# Shematic.net
KiCad netlist of a schematic drawn in EAGLE
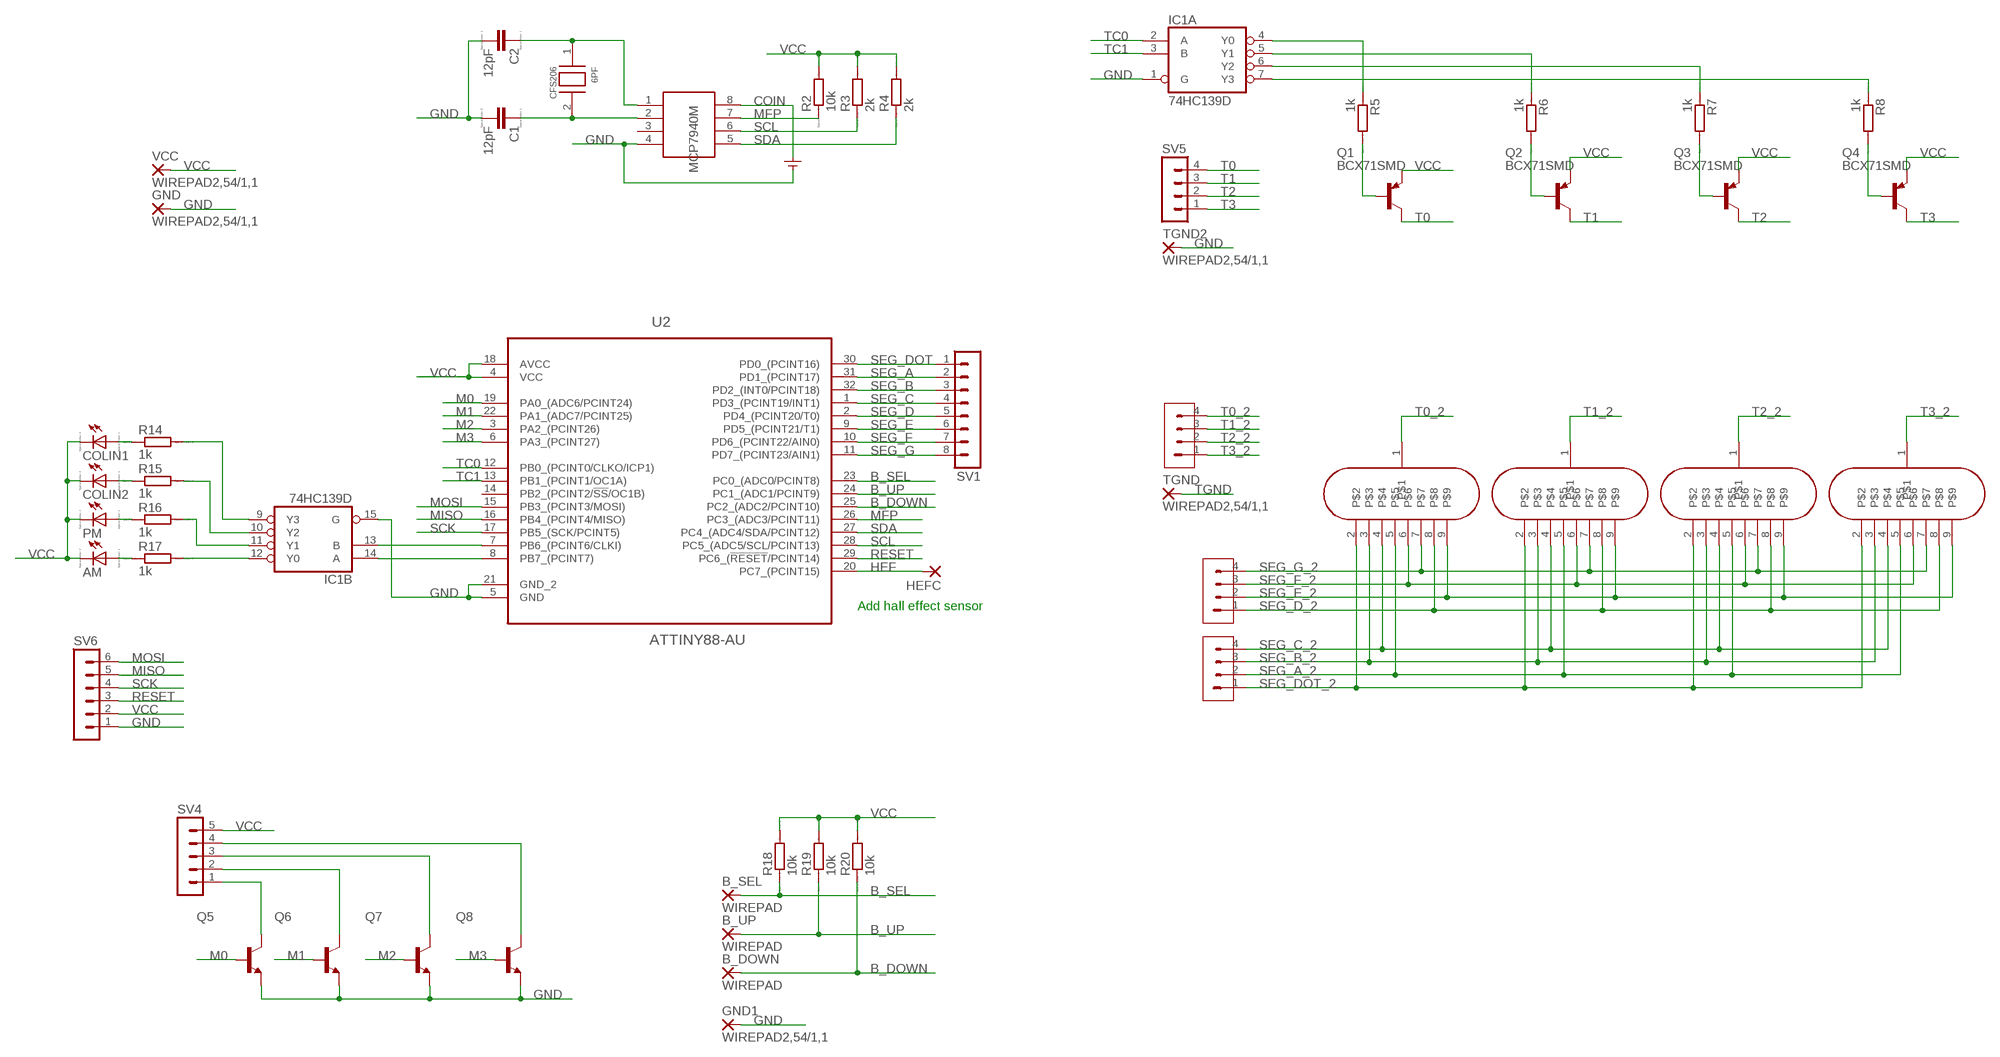
[diagram p0: schematic, sheet 1]

(export (version "E")
  (design (tool "Eeschema 10.0.6"))
  (components
    (comp (ref "6PF")
      (value "CFS206")
      (footprint "eagle-import:CFS206")
      (libsource (lib "eagle-import") (part "CFS206"))
    )
    (comp (ref "AM")
      (value "LED_ELD260")
      (footprint "eagle-import:LED_LD260")
      (libsource (lib "eagle-import") (part "LED_ELD260"))
    )
    (comp (ref "B_DOWN")
      (value "WIREPAD")
      (footprint "eagle-import:2,54_1,1")
      (libsource (lib "eagle-import") (part "WIREPAD2,54/1,1"))
    )
    (comp (ref "B_SEL")
      (value "WIREPAD")
      (footprint "eagle-import:2,54_1,1")
      (libsource (lib "eagle-import") (part "WIREPAD2,54/1,1"))
    )
    (comp (ref "B_UP")
      (value "WIREPAD")
      (footprint "eagle-import:2,54_1,1")
      (libsource (lib "eagle-import") (part "WIREPAD2,54/1,1"))
    )
    (comp (ref "C1")
      (value "12pF")
      (footprint "eagle-import:C1206")
      (libsource (lib "eagle-import") (part "CC1206"))
    )
    (comp (ref "C2")
      (value "12pF")
      (footprint "eagle-import:C1206")
      (libsource (lib "eagle-import") (part "CC1206"))
    )
    (comp (ref "COLIN1")
      (value "LED_ELD260")
      (footprint "eagle-import:LED_LD260")
      (libsource (lib "eagle-import") (part "LED_ELD260"))
    )
    (comp (ref "COLIN2")
      (value "LED_ELD260")
      (footprint "eagle-import:LED_LD260")
      (libsource (lib "eagle-import") (part "LED_ELD260"))
    )
    (comp (ref "GND")
      (value "WIREPAD2,54/1,1")
      (footprint "eagle-import:2,54_1,1")
      (libsource (lib "eagle-import") (part "WIREPAD2,54/1,1"))
    )
    (comp (ref "GND1")
      (value "WIREPAD2,54/1,1")
      (footprint "eagle-import:2,54_1,1")
      (libsource (lib "eagle-import") (part "WIREPAD2,54/1,1"))
    )
    (comp (ref "HEFC")
      (value "WIREPAD2,54/1,1")
      (footprint "eagle-import:2,54_1,1")
      (libsource (lib "eagle-import") (part "WIREPAD2,54/1,1"))
    )
    (comp (ref "IC1")
      (value "74HC139D")
      (footprint "eagle-import:SO16")
      (libsource (lib "eagle-import") (part "74139DHC"))
    )
    (comp (ref "MCP7940M")
      (value "SOIC-8")
      (footprint "eagle-import:SOIC-8")
      (libsource (lib "eagle-import") (part "SOIC-8"))
    )
    (comp (ref "PM")
      (value "LED_ELD260")
      (footprint "eagle-import:LED_LD260")
      (libsource (lib "eagle-import") (part "LED_ELD260"))
    )
    (comp (ref "Q1")
      (value "BCX71SMD")
      (footprint "eagle-import:SOT23")
      (libsource (lib "eagle-import") (part "BCX71SMD"))
    )
    (comp (ref "Q2")
      (value "BCX71SMD")
      (footprint "eagle-import:SOT23")
      (libsource (lib "eagle-import") (part "BCX71SMD"))
    )
    (comp (ref "Q3")
      (value "BCX71SMD")
      (footprint "eagle-import:SOT23")
      (libsource (lib "eagle-import") (part "BCX71SMD"))
    )
    (comp (ref "Q4")
      (value "BCX71SMD")
      (footprint "eagle-import:SOT23")
      (libsource (lib "eagle-import") (part "BCX71SMD"))
    )
    (comp (ref "Q5")
      (value "BCX70SMD")
      (footprint "eagle-import:SOT23")
      (libsource (lib "eagle-import") (part "BCX70SMD"))
    )
    (comp (ref "Q6")
      (value "BCX70SMD")
      (footprint "eagle-import:SOT23")
      (libsource (lib "eagle-import") (part "BCX70SMD"))
    )
    (comp (ref "Q7")
      (value "BCX70SMD")
      (footprint "eagle-import:SOT23")
      (libsource (lib "eagle-import") (part "BCX70SMD"))
    )
    (comp (ref "Q8")
      (value "BCX70SMD")
      (footprint "eagle-import:SOT23")
      (libsource (lib "eagle-import") (part "BCX70SMD"))
    )
    (comp (ref "R2")
      (value "10k")
      (footprint "eagle-import:R1206")
      (libsource (lib "eagle-import") (part "RR1206"))
    )
    (comp (ref "R3")
      (value "2k")
      (footprint "eagle-import:R1206")
      (libsource (lib "eagle-import") (part "RR1206"))
    )
    (comp (ref "R4")
      (value "2k")
      (footprint "eagle-import:R1206")
      (libsource (lib "eagle-import") (part "RR1206"))
    )
    (comp (ref "R5")
      (value "1k")
      (footprint "eagle-import:R1206")
      (libsource (lib "eagle-import") (part "RR1206"))
    )
    (comp (ref "R6")
      (value "1k")
      (footprint "eagle-import:R1206")
      (libsource (lib "eagle-import") (part "RR1206"))
    )
    (comp (ref "R7")
      (value "1k")
      (footprint "eagle-import:R1206")
      (libsource (lib "eagle-import") (part "RR1206"))
    )
    (comp (ref "R8")
      (value "1k")
      (footprint "eagle-import:R1206")
      (libsource (lib "eagle-import") (part "RR1206"))
    )
    (comp (ref "R14")
      (value "1k")
      (footprint "eagle-import:R1206")
      (libsource (lib "eagle-import") (part "RR1206"))
    )
    (comp (ref "R15")
      (value "1k")
      (footprint "eagle-import:R1206")
      (libsource (lib "eagle-import") (part "RR1206"))
    )
    (comp (ref "R16")
      (value "1k")
      (footprint "eagle-import:R1206")
      (libsource (lib "eagle-import") (part "RR1206"))
    )
    (comp (ref "R17")
      (value "1k")
      (footprint "eagle-import:R1206")
      (libsource (lib "eagle-import") (part "RR1206"))
    )
    (comp (ref "R18")
      (value "10k")
      (footprint "eagle-import:R1206")
      (libsource (lib "eagle-import") (part "RR1206"))
    )
    (comp (ref "R19")
      (value "10k")
      (footprint "eagle-import:R1206")
      (libsource (lib "eagle-import") (part "RR1206"))
    )
    (comp (ref "R20")
      (value "10k")
      (footprint "eagle-import:R1206")
      (libsource (lib "eagle-import") (part "RR1206"))
    )
    (comp (ref "SV1")
      (value "MA08-1")
      (footprint "eagle-import:MA08-1")
      (libsource (lib "eagle-import") (part "MA08-1"))
    )
    (comp (ref "SV2")
      (value "H04")
      (footprint "eagle-import:H04")
      (libsource (lib "eagle-import") (part "H04"))
    )
    (comp (ref "SV3")
      (value "H04")
      (footprint "eagle-import:H04")
      (libsource (lib "eagle-import") (part "H04"))
    )
    (comp (ref "SV4")
      (value "MA05-1")
      (footprint "eagle-import:MA05-1")
      (libsource (lib "eagle-import") (part "MA05-1"))
    )
    (comp (ref "SV5")
      (value "MA04-1")
      (footprint "eagle-import:MA04-1")
      (libsource (lib "eagle-import") (part "MA04-1"))
    )
    (comp (ref "SV6")
      (value "MA06-1")
      (footprint "eagle-import:MA06-1")
      (libsource (lib "eagle-import") (part "MA06-1"))
    )
    (comp (ref "SV7")
      (value "H04")
      (footprint "eagle-import:H04")
      (libsource (lib "eagle-import") (part "H04"))
    )
    (comp (ref "TGND")
      (value "WIREPAD2,54/1,1")
      (footprint "eagle-import:2,54_1,1")
      (libsource (lib "eagle-import") (part "WIREPAD2,54/1,1"))
    )
    (comp (ref "TGND2")
      (value "WIREPAD2,54/1,1")
      (footprint "eagle-import:2,54_1,1")
      (libsource (lib "eagle-import") (part "WIREPAD2,54/1,1"))
    )
    (comp (ref "TUBE0")
      (value "IV-9")
      (footprint "eagle-import:IV-9")
      (libsource (lib "eagle-import") (part "IV-9"))
    )
    (comp (ref "TUBE1")
      (value "IV-9")
      (footprint "eagle-import:IV-9")
      (libsource (lib "eagle-import") (part "IV-9"))
    )
    (comp (ref "TUBE2")
      (value "IV-9")
      (footprint "eagle-import:IV-9")
      (libsource (lib "eagle-import") (part "IV-9"))
    )
    (comp (ref "TUBE3")
      (value "IV-9")
      (footprint "eagle-import:IV-9")
      (libsource (lib "eagle-import") (part "IV-9"))
    )
    (comp (ref "U$5")
      (value "COIN")
      (footprint "eagle-import:COIN")
      (libsource (lib "eagle-import") (part "COIN"))
    )
    (comp (ref "U2")
      (value "ATTINY88-AU")
      (footprint "eagle-import:QFP80P900X900X120-32N")
      (libsource (lib "eagle-import") (part "ATTINY88-AU"))
    )
    (comp (ref "VCC")
      (value "WIREPAD2,54/1,1")
      (footprint "eagle-import:2,54_1,1")
      (libsource (lib "eagle-import") (part "WIREPAD2,54/1,1"))
    )
  )
  (nets
    (net (code "1") (name "/B_DOWN") (class "Default")
      (node (ref "B_DOWN") (pin "1") (pinfunction "P_1") (pintype "passive"))
      (node (ref "R20") (pin "1") (pinfunction "1_1") (pintype "passive"))
      (node (ref "U2") (pin "25") (pinfunction "PC2_(ADC2/PCINT10)_25") (pintype "bidirectional"))
    )
    (net (code "2") (name "/B_SEL") (class "Default")
      (node (ref "B_SEL") (pin "1") (pinfunction "P_1") (pintype "passive"))
      (node (ref "R18") (pin "1") (pinfunction "1_1") (pintype "passive"))
      (node (ref "U2") (pin "23") (pinfunction "PC0_(ADC0/PCINT8)_23") (pintype "bidirectional"))
    )
    (net (code "3") (name "/B_UP") (class "Default")
      (node (ref "B_UP") (pin "1") (pinfunction "P_1") (pintype "passive"))
      (node (ref "R19") (pin "1") (pinfunction "1_1") (pintype "passive"))
      (node (ref "U2") (pin "24") (pinfunction "PC1_(ADC1/PCINT9)_24") (pintype "bidirectional"))
    )
    (net (code "4") (name "/COIN") (class "Default")
      (node (ref "MCP7940M") (pin "8") (pinfunction "P$8_8") (pintype "bidirectional"))
      (node (ref "U$5") (pin "V+") (pinfunction "V+_V+") (pintype "bidirectional"))
    )
    (net (code "5") (name "/GND") (class "Default")
      (node (ref "C1") (pin "2") (pinfunction "2_2") (pintype "passive"))
      (node (ref "C2") (pin "2") (pinfunction "2_2") (pintype "passive"))
      (node (ref "GND") (pin "1") (pinfunction "P_1") (pintype "passive"))
      (node (ref "GND1") (pin "1") (pinfunction "P_1") (pintype "passive"))
      (node (ref "IC1") (pin "1") (pinfunction "G_1") (pintype "input"))
      (node (ref "IC1") (pin "15") (pinfunction "G_15") (pintype "input"))
      (node (ref "MCP7940M") (pin "4") (pinfunction "P$4_4") (pintype "bidirectional"))
      (node (ref "Q5") (pin "2") (pinfunction "E_2") (pintype "passive"))
      (node (ref "Q6") (pin "2") (pinfunction "E_2") (pintype "passive"))
      (node (ref "Q7") (pin "2") (pinfunction "E_2") (pintype "passive"))
      (node (ref "Q8") (pin "2") (pinfunction "E_2") (pintype "passive"))
      (node (ref "SV6") (pin "1") (pinfunction "1_1") (pintype "passive"))
      (node (ref "TGND2") (pin "1") (pinfunction "P_1") (pintype "passive"))
      (node (ref "U$5") (pin "V-") (pinfunction "V-_V-") (pintype "bidirectional"))
      (node (ref "U2") (pin "21") (pinfunction "GND_2_21") (pintype "passive"))
      (node (ref "U2") (pin "5") (pinfunction "GND_5") (pintype "passive"))
    )
    (net (code "6") (name "/HEF") (class "Default")
      (node (ref "HEFC") (pin "1") (pinfunction "P_1") (pintype "passive"))
      (node (ref "U2") (pin "20") (pinfunction "PC7_(PCINT15)_20") (pintype "bidirectional"))
    )
    (net (code "7") (name "/M0") (class "Default")
      (node (ref "Q5") (pin "1") (pinfunction "B_1") (pintype "passive"))
      (node (ref "U2") (pin "19") (pinfunction "PA0_(ADC6/PCINT24)_19") (pintype "bidirectional"))
    )
    (net (code "8") (name "/M1") (class "Default")
      (node (ref "Q6") (pin "1") (pinfunction "B_1") (pintype "passive"))
      (node (ref "U2") (pin "22") (pinfunction "PA1_(ADC7/PCINT25)_22") (pintype "bidirectional"))
    )
    (net (code "9") (name "/M2") (class "Default")
      (node (ref "Q7") (pin "1") (pinfunction "B_1") (pintype "passive"))
      (node (ref "U2") (pin "3") (pinfunction "PA2_(PCINT26)_3") (pintype "bidirectional"))
    )
    (net (code "10") (name "/M3") (class "Default")
      (node (ref "Q8") (pin "1") (pinfunction "B_1") (pintype "passive"))
      (node (ref "U2") (pin "6") (pinfunction "PA3_(PCINT27)_6") (pintype "bidirectional"))
    )
    (net (code "11") (name "/MFP") (class "Default")
      (node (ref "MCP7940M") (pin "7") (pinfunction "P$7_7") (pintype "bidirectional"))
      (node (ref "R2") (pin "1") (pinfunction "1_1") (pintype "passive"))
      (node (ref "U2") (pin "26") (pinfunction "PC3_(ADC3/PCINT11)_26") (pintype "bidirectional"))
    )
    (net (code "12") (name "/MISO") (class "Default")
      (node (ref "SV6") (pin "5") (pinfunction "5_5") (pintype "passive"))
      (node (ref "U2") (pin "16") (pinfunction "PB4_(PCINT4/MISO)_16") (pintype "bidirectional"))
    )
    (net (code "13") (name "/MOSI") (class "Default")
      (node (ref "SV6") (pin "6") (pinfunction "6_6") (pintype "passive"))
      (node (ref "U2") (pin "15") (pinfunction "PB3_(PCINT3/MOSI)_15") (pintype "bidirectional"))
    )
    (net (code "14") (name "/RESET") (class "Default")
      (node (ref "SV6") (pin "3") (pinfunction "3_3") (pintype "passive"))
      (node (ref "U2") (pin "29") (pinfunction "PC6_(~{RESET}/PCINT14)_29") (pintype "bidirectional"))
    )
    (net (code "15") (name "/SCK") (class "Default")
      (node (ref "SV6") (pin "4") (pinfunction "4_4") (pintype "passive"))
      (node (ref "U2") (pin "17") (pinfunction "PB5_(SCK/PCINT5)_17") (pintype "bidirectional"))
    )
    (net (code "16") (name "/SCL") (class "Default")
      (node (ref "MCP7940M") (pin "6") (pinfunction "P$6_6") (pintype "bidirectional"))
      (node (ref "R3") (pin "1") (pinfunction "1_1") (pintype "passive"))
      (node (ref "U2") (pin "28") (pinfunction "PC5_(ADC5/SCL/PCINT13)_28") (pintype "bidirectional"))
    )
    (net (code "17") (name "/SDA") (class "Default")
      (node (ref "MCP7940M") (pin "5") (pinfunction "P$5_5") (pintype "bidirectional"))
      (node (ref "R4") (pin "1") (pinfunction "1_1") (pintype "passive"))
      (node (ref "U2") (pin "27") (pinfunction "PC4_(ADC4/SDA/PCINT12)_27") (pintype "bidirectional"))
    )
    (net (code "18") (name "/SEG_A") (class "Default")
      (node (ref "SV1") (pin "2") (pinfunction "2_2") (pintype "passive"))
      (node (ref "U2") (pin "31") (pinfunction "PD1_(PCINT17)_31") (pintype "bidirectional"))
    )
    (net (code "19") (name "/SEG_A_2") (class "Default")
      (node (ref "SV7") (pin "2") (pinfunction "2_2") (pintype "bidirectional"))
      (node (ref "TUBE0") (pin "5") (pinfunction "P$5_5") (pintype "bidirectional"))
      (node (ref "TUBE1") (pin "5") (pinfunction "P$5_5") (pintype "bidirectional"))
      (node (ref "TUBE2") (pin "5") (pinfunction "P$5_5") (pintype "bidirectional"))
      (node (ref "TUBE3") (pin "5") (pinfunction "P$5_5") (pintype "bidirectional"))
    )
    (net (code "20") (name "/SEG_B") (class "Default")
      (node (ref "SV1") (pin "3") (pinfunction "3_3") (pintype "passive"))
      (node (ref "U2") (pin "32") (pinfunction "PD2_(INT0/PCINT18)_32") (pintype "bidirectional"))
    )
    (net (code "21") (name "/SEG_B_2") (class "Default")
      (node (ref "SV7") (pin "3") (pinfunction "3_3") (pintype "bidirectional"))
      (node (ref "TUBE0") (pin "3") (pinfunction "P$3_3") (pintype "bidirectional"))
      (node (ref "TUBE1") (pin "3") (pinfunction "P$3_3") (pintype "bidirectional"))
      (node (ref "TUBE2") (pin "3") (pinfunction "P$3_3") (pintype "bidirectional"))
      (node (ref "TUBE3") (pin "3") (pinfunction "P$3_3") (pintype "bidirectional"))
    )
    (net (code "22") (name "/SEG_C") (class "Default")
      (node (ref "SV1") (pin "4") (pinfunction "4_4") (pintype "passive"))
      (node (ref "U2") (pin "1") (pinfunction "PD3_(PCINT19/INT1)_1") (pintype "bidirectional"))
    )
    (net (code "23") (name "/SEG_C_2") (class "Default")
      (node (ref "SV7") (pin "4") (pinfunction "4_4") (pintype "bidirectional"))
      (node (ref "TUBE0") (pin "4") (pinfunction "P$4_4") (pintype "bidirectional"))
      (node (ref "TUBE1") (pin "4") (pinfunction "P$4_4") (pintype "bidirectional"))
      (node (ref "TUBE2") (pin "4") (pinfunction "P$4_4") (pintype "bidirectional"))
      (node (ref "TUBE3") (pin "4") (pinfunction "P$4_4") (pintype "bidirectional"))
    )
    (net (code "24") (name "/SEG_D") (class "Default")
      (node (ref "SV1") (pin "5") (pinfunction "5_5") (pintype "passive"))
      (node (ref "U2") (pin "2") (pinfunction "PD4_(PCINT20/T0)_2") (pintype "bidirectional"))
    )
    (net (code "25") (name "/SEG_DOT") (class "Default")
      (node (ref "SV1") (pin "1") (pinfunction "1_1") (pintype "passive"))
      (node (ref "U2") (pin "30") (pinfunction "PD0_(PCINT16)_30") (pintype "bidirectional"))
    )
    (net (code "26") (name "/SEG_DOT_2") (class "Default")
      (node (ref "SV7") (pin "1") (pinfunction "1_1") (pintype "bidirectional"))
      (node (ref "TUBE0") (pin "2") (pinfunction "P$2_2") (pintype "bidirectional"))
      (node (ref "TUBE1") (pin "2") (pinfunction "P$2_2") (pintype "bidirectional"))
      (node (ref "TUBE2") (pin "2") (pinfunction "P$2_2") (pintype "bidirectional"))
      (node (ref "TUBE3") (pin "2") (pinfunction "P$2_2") (pintype "bidirectional"))
    )
    (net (code "27") (name "/SEG_D_2") (class "Default")
      (node (ref "SV2") (pin "1") (pinfunction "1_1") (pintype "bidirectional"))
      (node (ref "TUBE0") (pin "8") (pinfunction "P$8_8") (pintype "bidirectional"))
      (node (ref "TUBE1") (pin "8") (pinfunction "P$8_8") (pintype "bidirectional"))
      (node (ref "TUBE2") (pin "8") (pinfunction "P$8_8") (pintype "bidirectional"))
      (node (ref "TUBE3") (pin "8") (pinfunction "P$8_8") (pintype "bidirectional"))
    )
    (net (code "28") (name "/SEG_E") (class "Default")
      (node (ref "SV1") (pin "6") (pinfunction "6_6") (pintype "passive"))
      (node (ref "U2") (pin "9") (pinfunction "PD5_(PCINT21/T1)_9") (pintype "bidirectional"))
    )
    (net (code "29") (name "/SEG_E_2") (class "Default")
      (node (ref "SV2") (pin "2") (pinfunction "2_2") (pintype "bidirectional"))
      (node (ref "TUBE0") (pin "9") (pinfunction "P$9_9") (pintype "bidirectional"))
      (node (ref "TUBE1") (pin "9") (pinfunction "P$9_9") (pintype "bidirectional"))
      (node (ref "TUBE2") (pin "9") (pinfunction "P$9_9") (pintype "bidirectional"))
      (node (ref "TUBE3") (pin "9") (pinfunction "P$9_9") (pintype "bidirectional"))
    )
    (net (code "30") (name "/SEG_F") (class "Default")
      (node (ref "SV1") (pin "7") (pinfunction "7_7") (pintype "passive"))
      (node (ref "U2") (pin "10") (pinfunction "PD6_(PCINT22/AIN0)_10") (pintype "bidirectional"))
    )
    (net (code "31") (name "/SEG_F_2") (class "Default")
      (node (ref "SV2") (pin "3") (pinfunction "3_3") (pintype "bidirectional"))
      (node (ref "TUBE0") (pin "6") (pinfunction "P$6_6") (pintype "bidirectional"))
      (node (ref "TUBE1") (pin "6") (pinfunction "P$6_6") (pintype "bidirectional"))
      (node (ref "TUBE2") (pin "6") (pinfunction "P$6_6") (pintype "bidirectional"))
      (node (ref "TUBE3") (pin "6") (pinfunction "P$6_6") (pintype "bidirectional"))
    )
    (net (code "32") (name "/SEG_G") (class "Default")
      (node (ref "SV1") (pin "8") (pinfunction "8_8") (pintype "passive"))
      (node (ref "U2") (pin "11") (pinfunction "PD7_(PCINT23/AIN1)_11") (pintype "bidirectional"))
    )
    (net (code "33") (name "/SEG_G_2") (class "Default")
      (node (ref "SV2") (pin "4") (pinfunction "4_4") (pintype "bidirectional"))
      (node (ref "TUBE0") (pin "7") (pinfunction "P$7_7") (pintype "bidirectional"))
      (node (ref "TUBE1") (pin "7") (pinfunction "P$7_7") (pintype "bidirectional"))
      (node (ref "TUBE2") (pin "7") (pinfunction "P$7_7") (pintype "bidirectional"))
      (node (ref "TUBE3") (pin "7") (pinfunction "P$7_7") (pintype "bidirectional"))
    )
    (net (code "34") (name "/T0") (class "Default")
      (node (ref "Q1") (pin "3") (pinfunction "C_3") (pintype "passive"))
      (node (ref "SV5") (pin "4") (pinfunction "4_4") (pintype "passive"))
    )
    (net (code "35") (name "/T0_2") (class "Default")
      (node (ref "SV3") (pin "4") (pinfunction "4_4") (pintype "bidirectional"))
      (node (ref "TUBE0") (pin "1") (pinfunction "P$1_1") (pintype "bidirectional"))
    )
    (net (code "36") (name "/T1") (class "Default")
      (node (ref "Q2") (pin "3") (pinfunction "C_3") (pintype "passive"))
      (node (ref "SV5") (pin "3") (pinfunction "3_3") (pintype "passive"))
    )
    (net (code "37") (name "/T1_2") (class "Default")
      (node (ref "SV3") (pin "3") (pinfunction "3_3") (pintype "bidirectional"))
      (node (ref "TUBE1") (pin "1") (pinfunction "P$1_1") (pintype "bidirectional"))
    )
    (net (code "38") (name "/T2") (class "Default")
      (node (ref "Q3") (pin "3") (pinfunction "C_3") (pintype "passive"))
      (node (ref "SV5") (pin "2") (pinfunction "2_2") (pintype "passive"))
    )
    (net (code "39") (name "/T2_2") (class "Default")
      (node (ref "SV3") (pin "2") (pinfunction "2_2") (pintype "bidirectional"))
      (node (ref "TUBE2") (pin "1") (pinfunction "P$1_1") (pintype "bidirectional"))
    )
    (net (code "40") (name "/T3") (class "Default")
      (node (ref "Q4") (pin "3") (pinfunction "C_3") (pintype "passive"))
      (node (ref "SV5") (pin "1") (pinfunction "1_1") (pintype "passive"))
    )
    (net (code "41") (name "/T3_2") (class "Default")
      (node (ref "SV3") (pin "1") (pinfunction "1_1") (pintype "bidirectional"))
      (node (ref "TUBE3") (pin "1") (pinfunction "P$1_1") (pintype "bidirectional"))
    )
    (net (code "42") (name "/TC0") (class "Default")
      (node (ref "IC1") (pin "2") (pinfunction "A_2") (pintype "input"))
      (node (ref "U2") (pin "12") (pinfunction "PB0_(PCINT0/CLKO/ICP1)_12") (pintype "bidirectional"))
    )
    (net (code "43") (name "/TC1") (class "Default")
      (node (ref "IC1") (pin "3") (pinfunction "B_3") (pintype "input"))
      (node (ref "U2") (pin "13") (pinfunction "PB1_(PCINT1/OC1A)_13") (pintype "bidirectional"))
    )
    (net (code "44") (name "/TGND") (class "Default")
      (node (ref "TGND") (pin "1") (pinfunction "P_1") (pintype "passive"))
    )
    (net (code "45") (name "/VCC") (class "Default")
      (node (ref "AM") (pin "K") (pinfunction "C_K") (pintype "passive"))
      (node (ref "COLIN1") (pin "K") (pinfunction "C_K") (pintype "passive"))
      (node (ref "COLIN2") (pin "K") (pinfunction "C_K") (pintype "passive"))
      (node (ref "PM") (pin "K") (pinfunction "C_K") (pintype "passive"))
      (node (ref "Q1") (pin "2") (pinfunction "E_2") (pintype "passive"))
      (node (ref "Q2") (pin "2") (pinfunction "E_2") (pintype "passive"))
      (node (ref "Q3") (pin "2") (pinfunction "E_2") (pintype "passive"))
      (node (ref "Q4") (pin "2") (pinfunction "E_2") (pintype "passive"))
      (node (ref "R18") (pin "2") (pinfunction "2_2") (pintype "passive"))
      (node (ref "R19") (pin "2") (pinfunction "2_2") (pintype "passive"))
      (node (ref "R2") (pin "2") (pinfunction "2_2") (pintype "passive"))
      (node (ref "R20") (pin "2") (pinfunction "2_2") (pintype "passive"))
      (node (ref "R3") (pin "2") (pinfunction "2_2") (pintype "passive"))
      (node (ref "R4") (pin "2") (pinfunction "2_2") (pintype "passive"))
      (node (ref "SV4") (pin "5") (pinfunction "5_5") (pintype "passive"))
      (node (ref "SV6") (pin "2") (pinfunction "2_2") (pintype "passive"))
      (node (ref "U2") (pin "18") (pinfunction "AVCC_18") (pintype "power_in"))
      (node (ref "U2") (pin "4") (pinfunction "VCC_4") (pintype "power_in"))
      (node (ref "VCC") (pin "1") (pinfunction "P_1") (pintype "passive"))
    )
    (net (code "46") (name "Net-(6PF-P$1)") (class "Default")
      (node (ref "6PF") (pin "1") (pinfunction "P$1_1") (pintype "bidirectional"))
      (node (ref "C2") (pin "1") (pinfunction "1_1") (pintype "passive"))
      (node (ref "MCP7940M") (pin "1") (pinfunction "P$1_1") (pintype "bidirectional"))
    )
    (net (code "47") (name "Net-(6PF-P$2)") (class "Default")
      (node (ref "6PF") (pin "2") (pinfunction "P$2_2") (pintype "bidirectional"))
      (node (ref "C1") (pin "1") (pinfunction "1_1") (pintype "passive"))
      (node (ref "MCP7940M") (pin "2") (pinfunction "P$2_2") (pintype "bidirectional"))
    )
    (net (code "48") (name "Net-(AM-PadA)") (class "Default")
      (node (ref "AM") (pin "A") (pinfunction "A_A") (pintype "passive"))
      (node (ref "R17") (pin "1") (pinfunction "1_1") (pintype "passive"))
    )
    (net (code "49") (name "Net-(COLIN1-PadA)") (class "Default")
      (node (ref "COLIN1") (pin "A") (pinfunction "A_A") (pintype "passive"))
      (node (ref "R14") (pin "1") (pinfunction "1_1") (pintype "passive"))
    )
    (net (code "50") (name "Net-(COLIN2-PadA)") (class "Default")
      (node (ref "COLIN2") (pin "A") (pinfunction "A_A") (pintype "passive"))
      (node (ref "R15") (pin "1") (pinfunction "1_1") (pintype "passive"))
    )
    (net (code "51") (name "Net-(IC1A-Y0)") (class "Default")
      (node (ref "IC1") (pin "4") (pinfunction "Y0_4") (pintype "output"))
      (node (ref "R5") (pin "1") (pinfunction "1_1") (pintype "passive"))
    )
    (net (code "52") (name "Net-(IC1A-Y1)") (class "Default")
      (node (ref "IC1") (pin "5") (pinfunction "Y1_5") (pintype "output"))
      (node (ref "R6") (pin "1") (pinfunction "1_1") (pintype "passive"))
    )
    (net (code "53") (name "Net-(IC1A-Y2)") (class "Default")
      (node (ref "IC1") (pin "6") (pinfunction "Y2_6") (pintype "output"))
      (node (ref "R7") (pin "1") (pinfunction "1_1") (pintype "passive"))
    )
    (net (code "54") (name "Net-(IC1A-Y3)") (class "Default")
      (node (ref "IC1") (pin "7") (pinfunction "Y3_7") (pintype "output"))
      (node (ref "R8") (pin "1") (pinfunction "1_1") (pintype "passive"))
    )
    (net (code "55") (name "Net-(IC1B-A)") (class "Default")
      (node (ref "IC1") (pin "14") (pinfunction "A_14") (pintype "input"))
      (node (ref "U2") (pin "8") (pinfunction "PB7_(PCINT7)_8") (pintype "bidirectional"))
    )
    (net (code "56") (name "Net-(IC1B-B)") (class "Default")
      (node (ref "IC1") (pin "13") (pinfunction "B_13") (pintype "input"))
      (node (ref "U2") (pin "7") (pinfunction "PB6_(PCINT6/CLKI)_7") (pintype "bidirectional"))
    )
    (net (code "57") (name "Net-(IC1B-Y0)") (class "Default")
      (node (ref "IC1") (pin "12") (pinfunction "Y0_12") (pintype "output"))
      (node (ref "R17") (pin "2") (pinfunction "2_2") (pintype "passive"))
    )
    (net (code "58") (name "Net-(IC1B-Y1)") (class "Default")
      (node (ref "IC1") (pin "11") (pinfunction "Y1_11") (pintype "output"))
      (node (ref "R16") (pin "2") (pinfunction "2_2") (pintype "passive"))
    )
    (net (code "59") (name "Net-(IC1B-Y2)") (class "Default")
      (node (ref "IC1") (pin "10") (pinfunction "Y2_10") (pintype "output"))
      (node (ref "R15") (pin "2") (pinfunction "2_2") (pintype "passive"))
    )
    (net (code "60") (name "Net-(IC1B-Y3)") (class "Default")
      (node (ref "IC1") (pin "9") (pinfunction "Y3_9") (pintype "output"))
      (node (ref "R14") (pin "2") (pinfunction "2_2") (pintype "passive"))
    )
    (net (code "61") (name "Net-(PM-PadA)") (class "Default")
      (node (ref "PM") (pin "A") (pinfunction "A_A") (pintype "passive"))
      (node (ref "R16") (pin "1") (pinfunction "1_1") (pintype "passive"))
    )
    (net (code "62") (name "Net-(Q1-B)") (class "Default")
      (node (ref "Q1") (pin "1") (pinfunction "B_1") (pintype "passive"))
      (node (ref "R5") (pin "2") (pinfunction "2_2") (pintype "passive"))
    )
    (net (code "63") (name "Net-(Q2-B)") (class "Default")
      (node (ref "Q2") (pin "1") (pinfunction "B_1") (pintype "passive"))
      (node (ref "R6") (pin "2") (pinfunction "2_2") (pintype "passive"))
    )
    (net (code "64") (name "Net-(Q3-B)") (class "Default")
      (node (ref "Q3") (pin "1") (pinfunction "B_1") (pintype "passive"))
      (node (ref "R7") (pin "2") (pinfunction "2_2") (pintype "passive"))
    )
    (net (code "65") (name "Net-(Q4-B)") (class "Default")
      (node (ref "Q4") (pin "1") (pinfunction "B_1") (pintype "passive"))
      (node (ref "R8") (pin "2") (pinfunction "2_2") (pintype "passive"))
    )
    (net (code "66") (name "Net-(Q5-C)") (class "Default")
      (node (ref "Q5") (pin "3") (pinfunction "C_3") (pintype "passive"))
      (node (ref "SV4") (pin "1") (pinfunction "1_1") (pintype "passive"))
    )
    (net (code "67") (name "Net-(Q6-C)") (class "Default")
      (node (ref "Q6") (pin "3") (pinfunction "C_3") (pintype "passive"))
      (node (ref "SV4") (pin "2") (pinfunction "2_2") (pintype "passive"))
    )
    (net (code "68") (name "Net-(Q7-C)") (class "Default")
      (node (ref "Q7") (pin "3") (pinfunction "C_3") (pintype "passive"))
      (node (ref "SV4") (pin "3") (pinfunction "3_3") (pintype "passive"))
    )
    (net (code "69") (name "Net-(Q8-C)") (class "Default")
      (node (ref "Q8") (pin "3") (pinfunction "C_3") (pintype "passive"))
      (node (ref "SV4") (pin "4") (pinfunction "4_4") (pintype "passive"))
    )
    (net (code "70") (name "unconnected-(MCP7940M-P$3-Pad3)") (class "Default")
      (node (ref "MCP7940M") (pin "3") (pinfunction "P$3_3") (pintype "bidirectional"))
    )
    (net (code "71") (name "unconnected-(U2-PB2_(PCINT2{slash}~{SS}{slash}OC1B)-Pad14)") (class "Default")
      (node (ref "U2") (pin "14") (pinfunction "PB2_(PCINT2/~{SS}/OC1B)_14") (pintype "bidirectional"))
    )
  )
)
